# w65c265sxb_tms9118_dram.net
KiCad netlist of a schematic drawn in EAGLE
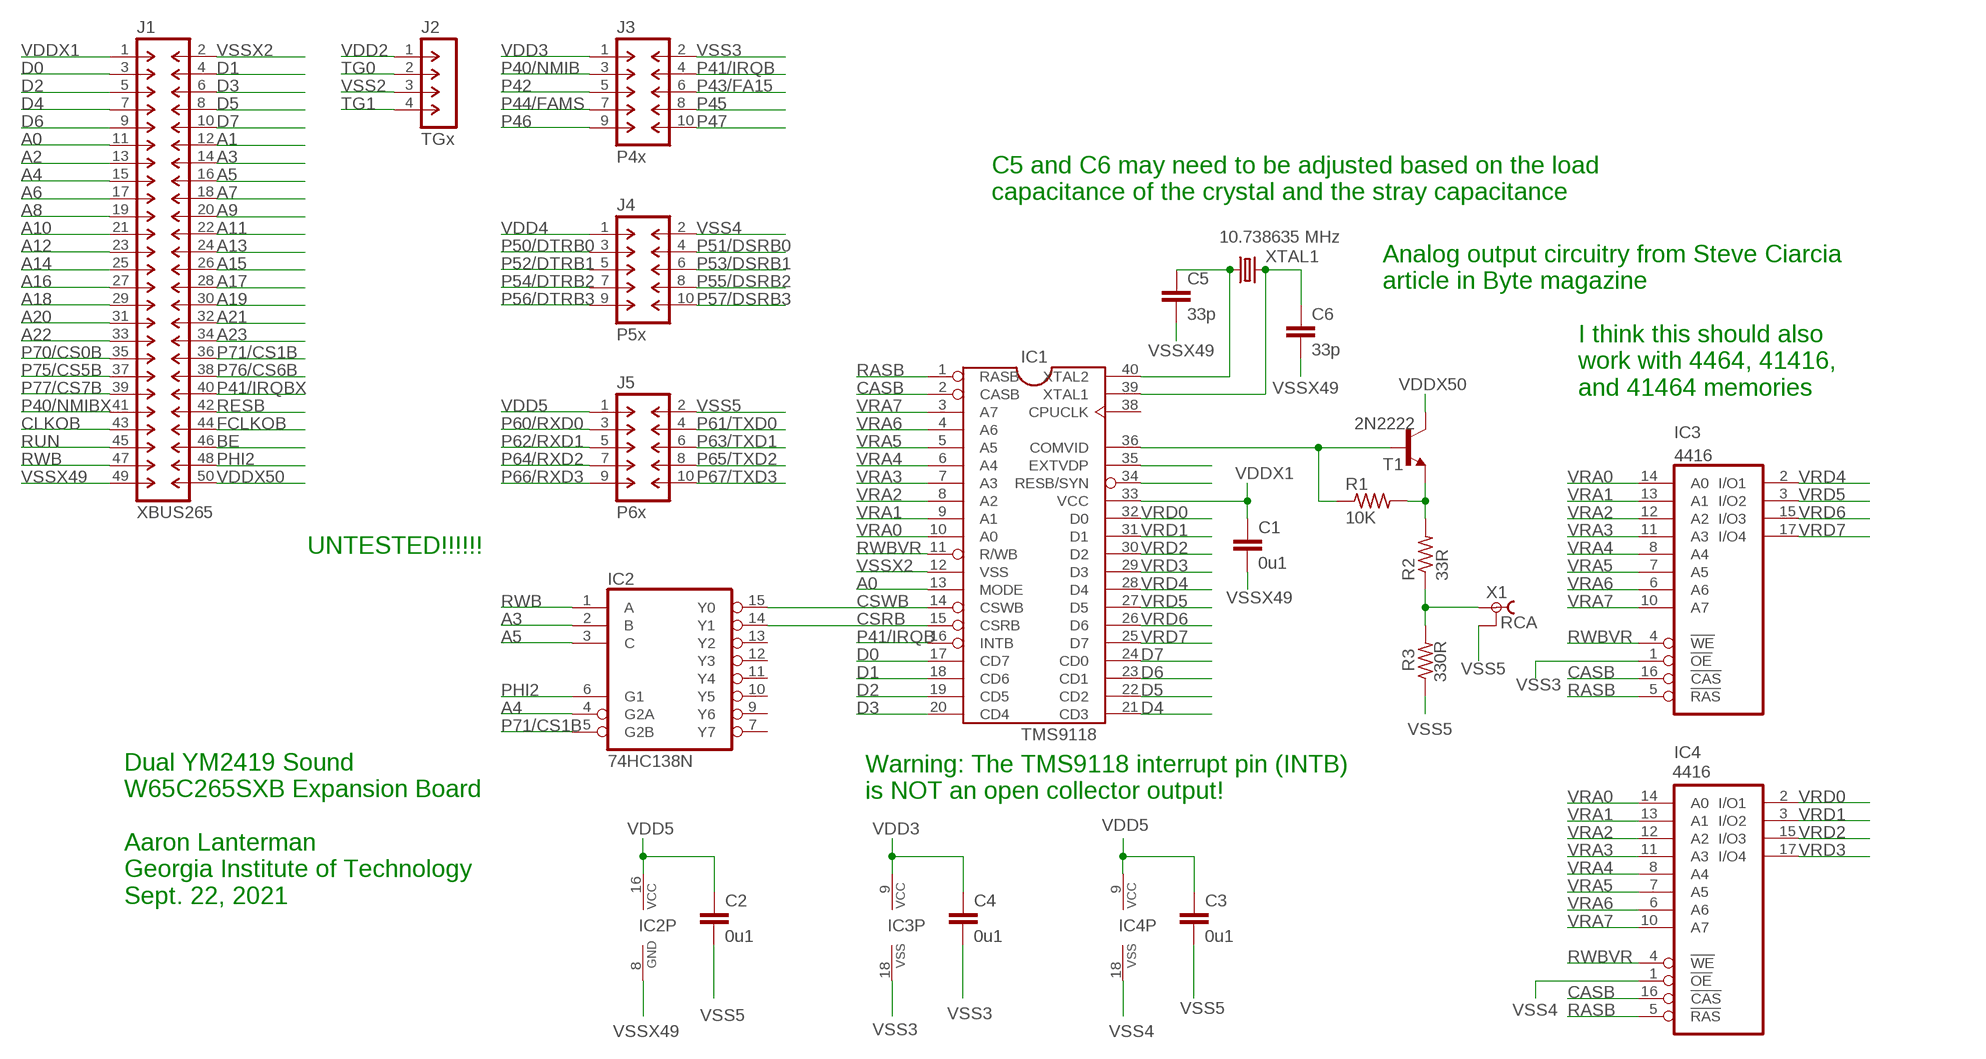
[diagram p0: schematic, sheet 1]

(export (version "E")
  (design (tool "Eeschema 10.0.6"))
  (components
    (comp (ref "C1")
      (value "0u1")
      (footprint "eagle-import:C050-025X075-AARON")
      (libsource (lib "eagle-import") (part "C-EU050-025X075-AARON"))
    )
    (comp (ref "C2")
      (value "0u1")
      (footprint "eagle-import:C050-025X075-AARON")
      (libsource (lib "eagle-import") (part "C-EU050-025X075-AARON"))
    )
    (comp (ref "C3")
      (value "0u1")
      (footprint "eagle-import:C050-025X075-AARON")
      (libsource (lib "eagle-import") (part "C-EU050-025X075-AARON"))
    )
    (comp (ref "C4")
      (value "0u1")
      (footprint "eagle-import:C050-025X075-AARON")
      (libsource (lib "eagle-import") (part "C-EU050-025X075-AARON"))
    )
    (comp (ref "C5")
      (value "33p")
      (footprint "eagle-import:C050-025X075-AARON")
      (libsource (lib "eagle-import") (part "C-EU050-025X075-AARON"))
    )
    (comp (ref "C6")
      (value "33p")
      (footprint "eagle-import:C050-025X075-AARON")
      (libsource (lib "eagle-import") (part "C-EU050-025X075-AARON"))
    )
    (comp (ref "IC1")
      (value "TMS9118")
      (footprint "eagle-import:DIL40")
      (libsource (lib "eagle-import") (part "TMS9118"))
    )
    (comp (ref "IC2")
      (value "74HC138N")
      (footprint "eagle-import:DIL16")
      (libsource (lib "eagle-import") (part "74138NHC"))
    )
    (comp (ref "IC3")
      (value "41464")
      (footprint "eagle-import:DIL18")
      (libsource (lib "eagle-import") (part "41464"))
    )
    (comp (ref "IC4")
      (value "41464")
      (footprint "eagle-import:DIL18")
      (libsource (lib "eagle-import") (part "41464"))
    )
    (comp (ref "J1")
      (value "XBUS265")
      (footprint "eagle-import:DIL-100-2X25")
      (libsource (lib "eagle-import") (part "M-2X25-DIL-100"))
    )
    (comp (ref "J2")
      (value "TGx")
      (footprint "eagle-import:SIP-100-04-40")
      (libsource (lib "eagle-import") (part "M-1X04-SIP-100-40"))
    )
    (comp (ref "J3")
      (value "P4x")
      (footprint "eagle-import:DIL-100-2X05")
      (libsource (lib "eagle-import") (part "M-2X05-DIL-100"))
    )
    (comp (ref "J4")
      (value "P5x")
      (footprint "eagle-import:DIL-100-2X05")
      (libsource (lib "eagle-import") (part "M-2X05-DIL-100"))
    )
    (comp (ref "J5")
      (value "P6x")
      (footprint "eagle-import:DIL-100-2X05")
      (libsource (lib "eagle-import") (part "M-2X05-DIL-100"))
    )
    (comp (ref "R1")
      (value "10K")
      (footprint "eagle-import:0207_10")
      (libsource (lib "eagle-import") (part "R-US_0207/10"))
    )
    (comp (ref "R2")
      (value "33R")
      (footprint "eagle-import:0207_10")
      (libsource (lib "eagle-import") (part "R-US_0207/10"))
    )
    (comp (ref "R3")
      (value "330R")
      (footprint "eagle-import:0207_10")
      (libsource (lib "eagle-import") (part "R-US_0207/10"))
    )
    (comp (ref "T1")
      (value "2N2222")
      (footprint "eagle-import:TO92-EBC-OVAL")
      (libsource (lib "eagle-import") (part "2N2222"))
    )
    (comp (ref "X1")
      (value "RCA")
      (footprint "eagle-import:TOBU3")
      (fields (field (name "MF") "FARNELL") (field (name "MPN") "TOBU 3"))
      (libsource (lib "eagle-import") (part "TOBU3"))
    )
    (comp (ref "XTAL1")
      (value "10.738635 MHz")
      (footprint "eagle-import:HC49_S")
      (libsource (lib "eagle-import") (part "CRYSTALHC49S"))
    )
  )
  (nets
    (net (code "1") (name "/A0") (class "Default")
      (node (ref "IC1") (pin "13") (pinfunction "MODE_13") (pintype "bidirectional"))
      (node (ref "J1") (pin "11") (pinfunction "11_11") (pintype "passive"))
    )
    (net (code "2") (name "/A1") (class "Default")
      (node (ref "J1") (pin "12") (pinfunction "12_12") (pintype "passive"))
    )
    (net (code "3") (name "/A2") (class "Default")
      (node (ref "J1") (pin "13") (pinfunction "13_13") (pintype "passive"))
    )
    (net (code "4") (name "/A3") (class "Default")
      (node (ref "IC2") (pin "2") (pinfunction "B_2") (pintype "input"))
      (node (ref "J1") (pin "14") (pinfunction "14_14") (pintype "passive"))
    )
    (net (code "5") (name "/A4") (class "Default")
      (node (ref "IC2") (pin "4") (pinfunction "G2A_4") (pintype "input"))
      (node (ref "J1") (pin "15") (pinfunction "15_15") (pintype "passive"))
    )
    (net (code "6") (name "/A5") (class "Default")
      (node (ref "IC2") (pin "3") (pinfunction "C_3") (pintype "input"))
      (node (ref "J1") (pin "16") (pinfunction "16_16") (pintype "passive"))
    )
    (net (code "7") (name "/A6") (class "Default")
      (node (ref "J1") (pin "17") (pinfunction "17_17") (pintype "passive"))
    )
    (net (code "8") (name "/A7") (class "Default")
      (node (ref "J1") (pin "18") (pinfunction "18_18") (pintype "passive"))
    )
    (net (code "9") (name "/A8") (class "Default")
      (node (ref "J1") (pin "19") (pinfunction "19_19") (pintype "passive"))
    )
    (net (code "10") (name "/A9") (class "Default")
      (node (ref "J1") (pin "20") (pinfunction "20_20") (pintype "passive"))
    )
    (net (code "11") (name "/A10") (class "Default")
      (node (ref "J1") (pin "21") (pinfunction "21_21") (pintype "passive"))
    )
    (net (code "12") (name "/A11") (class "Default")
      (node (ref "J1") (pin "22") (pinfunction "22_22") (pintype "passive"))
    )
    (net (code "13") (name "/A12") (class "Default")
      (node (ref "J1") (pin "23") (pinfunction "23_23") (pintype "passive"))
    )
    (net (code "14") (name "/A13") (class "Default")
      (node (ref "J1") (pin "24") (pinfunction "24_24") (pintype "passive"))
    )
    (net (code "15") (name "/A14") (class "Default")
      (node (ref "J1") (pin "25") (pinfunction "25_25") (pintype "passive"))
    )
    (net (code "16") (name "/A15") (class "Default")
      (node (ref "J1") (pin "26") (pinfunction "26_26") (pintype "passive"))
    )
    (net (code "17") (name "/A16") (class "Default")
      (node (ref "J1") (pin "27") (pinfunction "27_27") (pintype "passive"))
    )
    (net (code "18") (name "/A17") (class "Default")
      (node (ref "J1") (pin "28") (pinfunction "28_28") (pintype "passive"))
    )
    (net (code "19") (name "/A18") (class "Default")
      (node (ref "J1") (pin "29") (pinfunction "29_29") (pintype "passive"))
    )
    (net (code "20") (name "/A19") (class "Default")
      (node (ref "J1") (pin "30") (pinfunction "30_30") (pintype "passive"))
    )
    (net (code "21") (name "/A20") (class "Default")
      (node (ref "J1") (pin "31") (pinfunction "31_31") (pintype "passive"))
    )
    (net (code "22") (name "/A21") (class "Default")
      (node (ref "J1") (pin "32") (pinfunction "32_32") (pintype "passive"))
    )
    (net (code "23") (name "/A22") (class "Default")
      (node (ref "J1") (pin "33") (pinfunction "33_33") (pintype "passive"))
    )
    (net (code "24") (name "/A23") (class "Default")
      (node (ref "J1") (pin "34") (pinfunction "34_34") (pintype "passive"))
    )
    (net (code "25") (name "/BE") (class "Default")
      (node (ref "J1") (pin "46") (pinfunction "46_46") (pintype "passive"))
    )
    (net (code "26") (name "/CASB") (class "Default")
      (node (ref "IC1") (pin "2") (pinfunction "CASB_2") (pintype "bidirectional"))
      (node (ref "IC3") (pin "16") (pinfunction "~{CAS}_16") (pintype "input"))
      (node (ref "IC4") (pin "16") (pinfunction "~{CAS}_16") (pintype "input"))
    )
    (net (code "27") (name "/CLKOB") (class "Default")
      (node (ref "J1") (pin "43") (pinfunction "43_43") (pintype "passive"))
    )
    (net (code "28") (name "/CSRB") (class "Default")
      (node (ref "IC1") (pin "15") (pinfunction "CSRB_15") (pintype "bidirectional"))
      (node (ref "IC2") (pin "14") (pinfunction "Y1_14") (pintype "output"))
    )
    (net (code "29") (name "/CSWB") (class "Default")
      (node (ref "IC1") (pin "14") (pinfunction "CSWB_14") (pintype "bidirectional"))
      (node (ref "IC2") (pin "15") (pinfunction "Y0_15") (pintype "output"))
    )
    (net (code "30") (name "/D0") (class "Default")
      (node (ref "IC1") (pin "17") (pinfunction "CD7_17") (pintype "bidirectional"))
      (node (ref "J1") (pin "3") (pinfunction "3_3") (pintype "passive"))
    )
    (net (code "31") (name "/D1") (class "Default")
      (node (ref "IC1") (pin "18") (pinfunction "CD6_18") (pintype "bidirectional"))
      (node (ref "J1") (pin "4") (pinfunction "4_4") (pintype "passive"))
    )
    (net (code "32") (name "/D2") (class "Default")
      (node (ref "IC1") (pin "19") (pinfunction "CD5_19") (pintype "bidirectional"))
      (node (ref "J1") (pin "5") (pinfunction "5_5") (pintype "passive"))
    )
    (net (code "33") (name "/D3") (class "Default")
      (node (ref "IC1") (pin "20") (pinfunction "CD4_20") (pintype "bidirectional"))
      (node (ref "J1") (pin "6") (pinfunction "6_6") (pintype "passive"))
    )
    (net (code "34") (name "/D4") (class "Default")
      (node (ref "IC1") (pin "21") (pinfunction "CD3_21") (pintype "bidirectional"))
      (node (ref "J1") (pin "7") (pinfunction "7_7") (pintype "passive"))
    )
    (net (code "35") (name "/D5") (class "Default")
      (node (ref "IC1") (pin "22") (pinfunction "CD2_22") (pintype "bidirectional"))
      (node (ref "J1") (pin "8") (pinfunction "8_8") (pintype "passive"))
    )
    (net (code "36") (name "/D6") (class "Default")
      (node (ref "IC1") (pin "23") (pinfunction "CD1_23") (pintype "bidirectional"))
      (node (ref "J1") (pin "9") (pinfunction "9_9") (pintype "passive"))
    )
    (net (code "37") (name "/D7") (class "Default")
      (node (ref "IC1") (pin "24") (pinfunction "CD0_24") (pintype "bidirectional"))
      (node (ref "J1") (pin "10") (pinfunction "10_10") (pintype "passive"))
    )
    (net (code "38") (name "/FCLKOB") (class "Default")
      (node (ref "J1") (pin "44") (pinfunction "44_44") (pintype "passive"))
    )
    (net (code "39") (name "/P40{slash}NMIB") (class "Default")
      (node (ref "J3") (pin "3") (pinfunction "3_3") (pintype "passive"))
    )
    (net (code "40") (name "/P40{slash}NMIBX") (class "Default")
      (node (ref "J1") (pin "41") (pinfunction "41_41") (pintype "passive"))
    )
    (net (code "41") (name "/P41{slash}IRQB") (class "Default")
      (node (ref "IC1") (pin "16") (pinfunction "INTB_16") (pintype "bidirectional"))
      (node (ref "J3") (pin "4") (pinfunction "4_4") (pintype "passive"))
    )
    (net (code "42") (name "/P41{slash}IRQBX") (class "Default")
      (node (ref "J1") (pin "40") (pinfunction "40_40") (pintype "passive"))
    )
    (net (code "43") (name "/P42") (class "Default")
      (node (ref "J3") (pin "5") (pinfunction "5_5") (pintype "passive"))
    )
    (net (code "44") (name "/P43{slash}FA15") (class "Default")
      (node (ref "J3") (pin "6") (pinfunction "6_6") (pintype "passive"))
    )
    (net (code "45") (name "/P44{slash}FAMS") (class "Default")
      (node (ref "J3") (pin "7") (pinfunction "7_7") (pintype "passive"))
    )
    (net (code "46") (name "/P45") (class "Default")
      (node (ref "J3") (pin "8") (pinfunction "8_8") (pintype "passive"))
    )
    (net (code "47") (name "/P46") (class "Default")
      (node (ref "J3") (pin "9") (pinfunction "9_9") (pintype "passive"))
    )
    (net (code "48") (name "/P47") (class "Default")
      (node (ref "J3") (pin "10") (pinfunction "10_10") (pintype "passive"))
    )
    (net (code "49") (name "/P50{slash}DTRB0") (class "Default")
      (node (ref "J4") (pin "3") (pinfunction "3_3") (pintype "passive"))
    )
    (net (code "50") (name "/P51{slash}DSRB0") (class "Default")
      (node (ref "J4") (pin "4") (pinfunction "4_4") (pintype "passive"))
    )
    (net (code "51") (name "/P52{slash}DTRB1") (class "Default")
      (node (ref "J4") (pin "5") (pinfunction "5_5") (pintype "passive"))
    )
    (net (code "52") (name "/P53{slash}DSRB1") (class "Default")
      (node (ref "J4") (pin "6") (pinfunction "6_6") (pintype "passive"))
    )
    (net (code "53") (name "/P54{slash}DTRB2") (class "Default")
      (node (ref "J4") (pin "7") (pinfunction "7_7") (pintype "passive"))
    )
    (net (code "54") (name "/P55{slash}DSRB2") (class "Default")
      (node (ref "J4") (pin "8") (pinfunction "8_8") (pintype "passive"))
    )
    (net (code "55") (name "/P56{slash}DTRB3") (class "Default")
      (node (ref "J4") (pin "9") (pinfunction "9_9") (pintype "passive"))
    )
    (net (code "56") (name "/P57{slash}DSRB3") (class "Default")
      (node (ref "J4") (pin "10") (pinfunction "10_10") (pintype "passive"))
    )
    (net (code "57") (name "/P60{slash}RXD0") (class "Default")
      (node (ref "J5") (pin "3") (pinfunction "3_3") (pintype "passive"))
    )
    (net (code "58") (name "/P61{slash}TXD0") (class "Default")
      (node (ref "J5") (pin "4") (pinfunction "4_4") (pintype "passive"))
    )
    (net (code "59") (name "/P62{slash}RXD1") (class "Default")
      (node (ref "J5") (pin "5") (pinfunction "5_5") (pintype "passive"))
    )
    (net (code "60") (name "/P63{slash}TXD1") (class "Default")
      (node (ref "J5") (pin "6") (pinfunction "6_6") (pintype "passive"))
    )
    (net (code "61") (name "/P64{slash}RXD2") (class "Default")
      (node (ref "J5") (pin "7") (pinfunction "7_7") (pintype "passive"))
    )
    (net (code "62") (name "/P65{slash}TXD2") (class "Default")
      (node (ref "J5") (pin "8") (pinfunction "8_8") (pintype "passive"))
    )
    (net (code "63") (name "/P66{slash}RXD3") (class "Default")
      (node (ref "J5") (pin "9") (pinfunction "9_9") (pintype "passive"))
    )
    (net (code "64") (name "/P67{slash}TXD3") (class "Default")
      (node (ref "J5") (pin "10") (pinfunction "10_10") (pintype "passive"))
    )
    (net (code "65") (name "/P70{slash}CS0B") (class "Default")
      (node (ref "J1") (pin "35") (pinfunction "35_35") (pintype "passive"))
    )
    (net (code "66") (name "/P71{slash}CS1B") (class "Default")
      (node (ref "IC2") (pin "5") (pinfunction "G2B_5") (pintype "input"))
      (node (ref "J1") (pin "36") (pinfunction "36_36") (pintype "passive"))
    )
    (net (code "67") (name "/P75{slash}CS5B") (class "Default")
      (node (ref "J1") (pin "37") (pinfunction "37_37") (pintype "passive"))
    )
    (net (code "68") (name "/P76{slash}CS6B") (class "Default")
      (node (ref "J1") (pin "38") (pinfunction "38_38") (pintype "passive"))
    )
    (net (code "69") (name "/P77{slash}CS7B") (class "Default")
      (node (ref "J1") (pin "39") (pinfunction "39_39") (pintype "passive"))
    )
    (net (code "70") (name "/PHI2") (class "Default")
      (node (ref "IC2") (pin "6") (pinfunction "G1_6") (pintype "input"))
      (node (ref "J1") (pin "48") (pinfunction "48_48") (pintype "passive"))
    )
    (net (code "71") (name "/RASB") (class "Default")
      (node (ref "IC1") (pin "1") (pinfunction "RASB_1") (pintype "bidirectional"))
      (node (ref "IC3") (pin "5") (pinfunction "~{RAS}_5") (pintype "input"))
      (node (ref "IC4") (pin "5") (pinfunction "~{RAS}_5") (pintype "input"))
    )
    (net (code "72") (name "/RESB") (class "Default")
      (node (ref "J1") (pin "42") (pinfunction "42_42") (pintype "passive"))
    )
    (net (code "73") (name "/RUN") (class "Default")
      (node (ref "J1") (pin "45") (pinfunction "45_45") (pintype "passive"))
    )
    (net (code "74") (name "/RWB") (class "Default")
      (node (ref "IC2") (pin "1") (pinfunction "A_1") (pintype "input"))
      (node (ref "J1") (pin "47") (pinfunction "47_47") (pintype "passive"))
    )
    (net (code "75") (name "/RWBVR") (class "Default")
      (node (ref "IC1") (pin "11") (pinfunction "R/WB_11") (pintype "bidirectional"))
      (node (ref "IC3") (pin "4") (pinfunction "~{WE}_4") (pintype "input"))
      (node (ref "IC4") (pin "4") (pinfunction "~{WE}_4") (pintype "input"))
    )
    (net (code "76") (name "/TG0") (class "Default")
      (node (ref "J2") (pin "2") (pinfunction "2_2") (pintype "passive"))
    )
    (net (code "77") (name "/TG1") (class "Default")
      (node (ref "J2") (pin "4") (pinfunction "4_4") (pintype "passive"))
    )
    (net (code "78") (name "/VDD2") (class "Default")
      (node (ref "J2") (pin "1") (pinfunction "1_1") (pintype "passive"))
    )
    (net (code "79") (name "/VDD3") (class "Default")
      (node (ref "C4") (pin "1") (pinfunction "1_1") (pintype "passive"))
      (node (ref "IC3") (pin "9") (pinfunction "VCC_9") (pintype "power_in"))
      (node (ref "J3") (pin "1") (pinfunction "1_1") (pintype "passive"))
    )
    (net (code "80") (name "/VDD4") (class "Default")
      (node (ref "J4") (pin "1") (pinfunction "1_1") (pintype "passive"))
    )
    (net (code "81") (name "/VDD5") (class "Default")
      (node (ref "C2") (pin "1") (pinfunction "1_1") (pintype "passive"))
      (node (ref "C3") (pin "1") (pinfunction "1_1") (pintype "passive"))
      (node (ref "IC2") (pin "16") (pinfunction "VCC_16") (pintype "power_in"))
      (node (ref "IC4") (pin "9") (pinfunction "VCC_9") (pintype "power_in"))
      (node (ref "J5") (pin "1") (pinfunction "1_1") (pintype "passive"))
    )
    (net (code "82") (name "/VDDX1") (class "Default")
      (node (ref "C1") (pin "1") (pinfunction "1_1") (pintype "passive"))
      (node (ref "IC1") (pin "33") (pinfunction "VCC_33") (pintype "bidirectional"))
      (node (ref "J1") (pin "1") (pinfunction "1_1") (pintype "passive"))
    )
    (net (code "83") (name "/VDDX50") (class "Default")
      (node (ref "J1") (pin "50") (pinfunction "50_50") (pintype "passive"))
      (node (ref "T1") (pin "C") (pinfunction "C_C") (pintype "passive"))
    )
    (net (code "84") (name "/VRA0") (class "Default")
      (node (ref "IC1") (pin "10") (pinfunction "A0_10") (pintype "bidirectional"))
      (node (ref "IC3") (pin "14") (pinfunction "A0_14") (pintype "input"))
      (node (ref "IC4") (pin "14") (pinfunction "A0_14") (pintype "input"))
    )
    (net (code "85") (name "/VRA1") (class "Default")
      (node (ref "IC1") (pin "9") (pinfunction "A1_9") (pintype "bidirectional"))
      (node (ref "IC3") (pin "13") (pinfunction "A1_13") (pintype "input"))
      (node (ref "IC4") (pin "13") (pinfunction "A1_13") (pintype "input"))
    )
    (net (code "86") (name "/VRA2") (class "Default")
      (node (ref "IC1") (pin "8") (pinfunction "A2_8") (pintype "bidirectional"))
      (node (ref "IC3") (pin "12") (pinfunction "A2_12") (pintype "input"))
      (node (ref "IC4") (pin "12") (pinfunction "A2_12") (pintype "input"))
    )
    (net (code "87") (name "/VRA3") (class "Default")
      (node (ref "IC1") (pin "7") (pinfunction "A3_7") (pintype "bidirectional"))
      (node (ref "IC3") (pin "11") (pinfunction "A3_11") (pintype "input"))
      (node (ref "IC4") (pin "11") (pinfunction "A3_11") (pintype "input"))
    )
    (net (code "88") (name "/VRA4") (class "Default")
      (node (ref "IC1") (pin "6") (pinfunction "A4_6") (pintype "bidirectional"))
      (node (ref "IC3") (pin "8") (pinfunction "A4_8") (pintype "input"))
      (node (ref "IC4") (pin "8") (pinfunction "A4_8") (pintype "input"))
    )
    (net (code "89") (name "/VRA5") (class "Default")
      (node (ref "IC1") (pin "5") (pinfunction "A5_5") (pintype "bidirectional"))
      (node (ref "IC3") (pin "7") (pinfunction "A5_7") (pintype "input"))
      (node (ref "IC4") (pin "7") (pinfunction "A5_7") (pintype "input"))
    )
    (net (code "90") (name "/VRA6") (class "Default")
      (node (ref "IC1") (pin "4") (pinfunction "A6_4") (pintype "bidirectional"))
      (node (ref "IC3") (pin "6") (pinfunction "A6_6") (pintype "input"))
      (node (ref "IC4") (pin "6") (pinfunction "A6_6") (pintype "input"))
    )
    (net (code "91") (name "/VRA7") (class "Default")
      (node (ref "IC1") (pin "3") (pinfunction "A7_3") (pintype "bidirectional"))
      (node (ref "IC3") (pin "10") (pinfunction "A7_10") (pintype "input"))
      (node (ref "IC4") (pin "10") (pinfunction "A7_10") (pintype "input"))
    )
    (net (code "92") (name "/VRD0") (class "Default")
      (node (ref "IC1") (pin "32") (pinfunction "D0_32") (pintype "bidirectional"))
      (node (ref "IC4") (pin "2") (pinfunction "I/O1_2") (pintype "bidirectional"))
    )
    (net (code "93") (name "/VRD1") (class "Default")
      (node (ref "IC1") (pin "31") (pinfunction "D1_31") (pintype "bidirectional"))
      (node (ref "IC4") (pin "3") (pinfunction "I/O2_3") (pintype "bidirectional"))
    )
    (net (code "94") (name "/VRD2") (class "Default")
      (node (ref "IC1") (pin "30") (pinfunction "D2_30") (pintype "bidirectional"))
      (node (ref "IC4") (pin "15") (pinfunction "I/O3_15") (pintype "bidirectional"))
    )
    (net (code "95") (name "/VRD3") (class "Default")
      (node (ref "IC1") (pin "29") (pinfunction "D3_29") (pintype "bidirectional"))
      (node (ref "IC4") (pin "17") (pinfunction "I/O4_17") (pintype "bidirectional"))
    )
    (net (code "96") (name "/VRD4") (class "Default")
      (node (ref "IC1") (pin "28") (pinfunction "D4_28") (pintype "bidirectional"))
      (node (ref "IC3") (pin "2") (pinfunction "I/O1_2") (pintype "bidirectional"))
    )
    (net (code "97") (name "/VRD5") (class "Default")
      (node (ref "IC1") (pin "27") (pinfunction "D5_27") (pintype "bidirectional"))
      (node (ref "IC3") (pin "3") (pinfunction "I/O2_3") (pintype "bidirectional"))
    )
    (net (code "98") (name "/VRD6") (class "Default")
      (node (ref "IC1") (pin "26") (pinfunction "D6_26") (pintype "bidirectional"))
      (node (ref "IC3") (pin "15") (pinfunction "I/O3_15") (pintype "bidirectional"))
    )
    (net (code "99") (name "/VRD7") (class "Default")
      (node (ref "IC1") (pin "25") (pinfunction "D7_25") (pintype "bidirectional"))
      (node (ref "IC3") (pin "17") (pinfunction "I/O4_17") (pintype "bidirectional"))
    )
    (net (code "100") (name "/VSS2") (class "Default")
      (node (ref "J2") (pin "3") (pinfunction "3_3") (pintype "passive"))
    )
    (net (code "101") (name "/VSS3") (class "Default")
      (node (ref "C4") (pin "2") (pinfunction "2_2") (pintype "passive"))
      (node (ref "IC3") (pin "1") (pinfunction "~{OE}_1") (pintype "input"))
      (node (ref "IC3") (pin "18") (pinfunction "VSS_18") (pintype "power_in"))
      (node (ref "J3") (pin "2") (pinfunction "2_2") (pintype "passive"))
    )
    (net (code "102") (name "/VSS4") (class "Default")
      (node (ref "IC4") (pin "1") (pinfunction "~{OE}_1") (pintype "input"))
      (node (ref "IC4") (pin "18") (pinfunction "VSS_18") (pintype "power_in"))
      (node (ref "J4") (pin "2") (pinfunction "2_2") (pintype "passive"))
    )
    (net (code "103") (name "/VSS5") (class "Default")
      (node (ref "C2") (pin "2") (pinfunction "2_2") (pintype "passive"))
      (node (ref "C3") (pin "2") (pinfunction "2_2") (pintype "passive"))
      (node (ref "J5") (pin "2") (pinfunction "2_2") (pintype "passive"))
      (node (ref "R3") (pin "1") (pinfunction "1_1") (pintype "passive"))
      (node (ref "X1") (pin "2") (pinfunction "2_2") (pintype "passive"))
      (node (ref "X1") (pin "2@1") (pinfunction "2_2@1") (pintype "passive"))
      (node (ref "X1") (pin "2@2") (pinfunction "2_2@2") (pintype "passive"))
    )
    (net (code "104") (name "/VSSX2") (class "Default")
      (node (ref "IC1") (pin "12") (pinfunction "VSS_12") (pintype "bidirectional"))
      (node (ref "J1") (pin "2") (pinfunction "2_2") (pintype "passive"))
    )
    (net (code "105") (name "/VSSX49") (class "Default")
      (node (ref "C1") (pin "2") (pinfunction "2_2") (pintype "passive"))
      (node (ref "C5") (pin "2") (pinfunction "2_2") (pintype "passive"))
      (node (ref "C6") (pin "2") (pinfunction "2_2") (pintype "passive"))
      (node (ref "IC2") (pin "8") (pinfunction "GND_8") (pintype "power_in"))
      (node (ref "J1") (pin "49") (pinfunction "49_49") (pintype "passive"))
    )
    (net (code "106") (name "Net-(IC1-COMVID)") (class "Default")
      (node (ref "IC1") (pin "36") (pinfunction "COMVID_36") (pintype "bidirectional"))
      (node (ref "R1") (pin "1") (pinfunction "1_1") (pintype "passive"))
      (node (ref "T1") (pin "B") (pinfunction "B_B") (pintype "passive"))
    )
    (net (code "107") (name "Net-(IC1-XTAL1)") (class "Default")
      (node (ref "C6") (pin "1") (pinfunction "1_1") (pintype "passive"))
      (node (ref "IC1") (pin "39") (pinfunction "XTAL1_39") (pintype "bidirectional"))
      (node (ref "XTAL1") (pin "2") (pinfunction "2_2") (pintype "passive"))
    )
    (net (code "108") (name "Net-(IC1-XTAL2)") (class "Default")
      (node (ref "C5") (pin "1") (pinfunction "1_1") (pintype "passive"))
      (node (ref "IC1") (pin "40") (pinfunction "XTAL2_40") (pintype "bidirectional"))
      (node (ref "XTAL1") (pin "1") (pinfunction "1_1") (pintype "passive"))
    )
    (net (code "109") (name "Net-(R1-Pad2)") (class "Default")
      (node (ref "R1") (pin "2") (pinfunction "2_2") (pintype "passive"))
      (node (ref "R2") (pin "2") (pinfunction "2_2") (pintype "passive"))
      (node (ref "T1") (pin "E") (pinfunction "E_E") (pintype "passive"))
    )
    (net (code "110") (name "Net-(R2-Pad1)") (class "Default")
      (node (ref "R2") (pin "1") (pinfunction "1_1") (pintype "passive"))
      (node (ref "R3") (pin "2") (pinfunction "2_2") (pintype "passive"))
      (node (ref "X1") (pin "1") (pinfunction "1_1") (pintype "passive"))
    )
    (net (code "111") (name "unconnected-(IC1-CPUCLK-Pad38)") (class "Default")
      (node (ref "IC1") (pin "38") (pinfunction "CPUCLK_38") (pintype "bidirectional"))
    )
    (net (code "112") (name "unconnected-(IC1-EXTVDP-Pad35)") (class "Default")
      (node (ref "IC1") (pin "35") (pinfunction "EXTVDP_35") (pintype "bidirectional"))
    )
    (net (code "113") (name "unconnected-(IC1-RESB{slash}SYN-Pad34)") (class "Default")
      (node (ref "IC1") (pin "34") (pinfunction "RESB/SYN_34") (pintype "bidirectional"))
    )
    (net (code "114") (name "unconnected-(IC2A-Y2-Pad13)") (class "Default")
      (node (ref "IC2") (pin "13") (pinfunction "Y2_13") (pintype "output"))
    )
    (net (code "115") (name "unconnected-(IC2A-Y3-Pad12)") (class "Default")
      (node (ref "IC2") (pin "12") (pinfunction "Y3_12") (pintype "output"))
    )
    (net (code "116") (name "unconnected-(IC2A-Y4-Pad11)") (class "Default")
      (node (ref "IC2") (pin "11") (pinfunction "Y4_11") (pintype "output"))
    )
    (net (code "117") (name "unconnected-(IC2A-Y5-Pad10)") (class "Default")
      (node (ref "IC2") (pin "10") (pinfunction "Y5_10") (pintype "output"))
    )
    (net (code "118") (name "unconnected-(IC2A-Y6-Pad9)") (class "Default")
      (node (ref "IC2") (pin "9") (pinfunction "Y6_9") (pintype "output"))
    )
    (net (code "119") (name "unconnected-(IC2A-Y7-Pad7)") (class "Default")
      (node (ref "IC2") (pin "7") (pinfunction "Y7_7") (pintype "output"))
    )
  )
)
